# SCH_Arithmetic_Logic_Unit_2021-10-03.net
KiCad netlist of a schematic drawn in EasyEDA
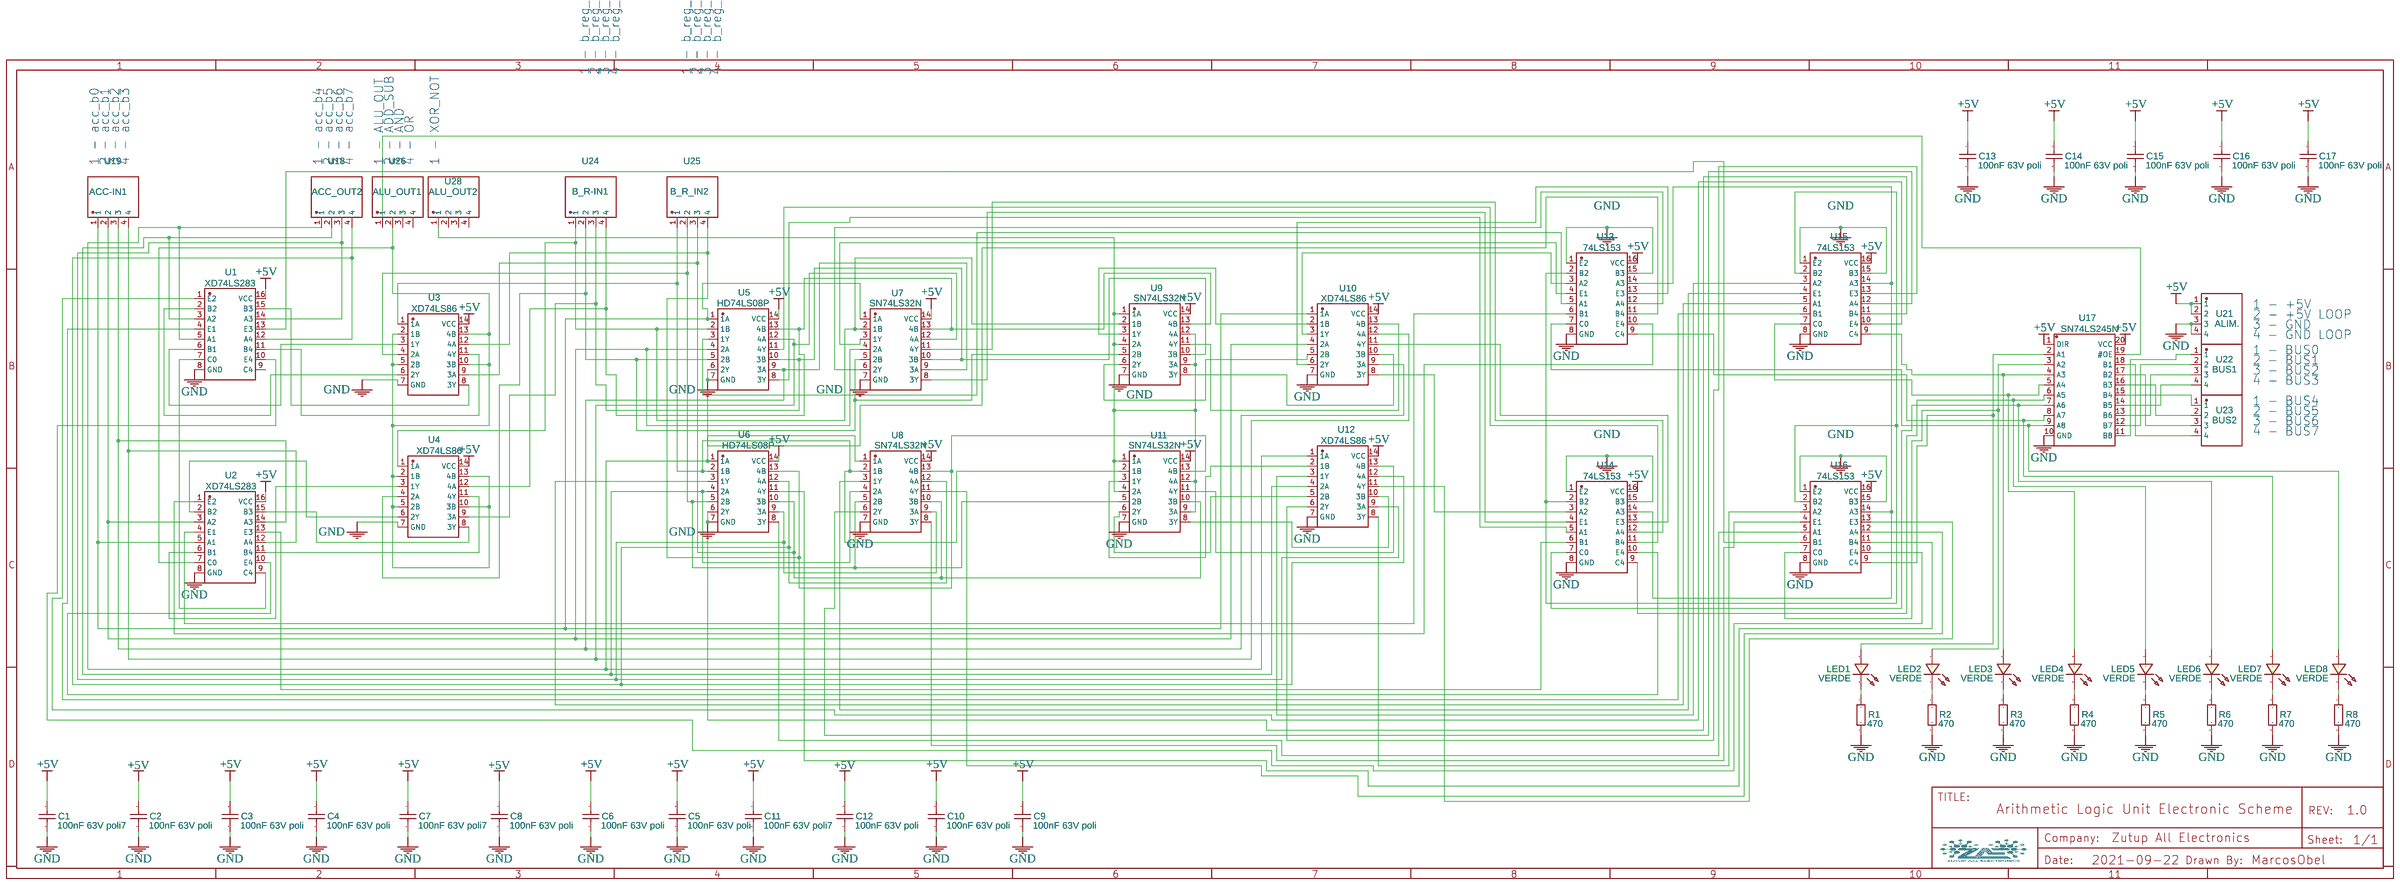
[diagram p0: schematic sheet]

(export (version "E")
  (design (tool "Eeschema 10.0.6"))
  (components
    (comp (ref "C1")
      (value "100nF 63V poli7")
      (fields
        (field (name "BOM_Manufacturer Part") "SR305C105KAR")
        (field (name "BOM_Supplier Part") "C444741")
      )
      (libsource (lib "") (part "SR305C105KAR"))
    )
    (comp (ref "C2")
      (value "100nF 63V poli")
      (fields
        (field (name "BOM_Manufacturer Part") "SR305C105KAR")
        (field (name "BOM_Supplier Part") "C444741")
      )
      (libsource (lib "") (part "SR305C105KAR"))
    )
    (comp (ref "C3")
      (value "100nF 63V poli")
      (fields
        (field (name "BOM_Manufacturer Part") "SR305C105KAR")
        (field (name "BOM_Supplier Part") "C444741")
      )
      (libsource (lib "") (part "SR305C105KAR"))
    )
    (comp (ref "C4")
      (value "100nF 63V poli")
      (fields
        (field (name "BOM_Manufacturer Part") "SR305C105KAR")
        (field (name "BOM_Supplier Part") "C444741")
      )
      (libsource (lib "") (part "SR305C105KAR"))
    )
    (comp (ref "C5")
      (value "100nF 63V poli")
      (fields
        (field (name "BOM_Manufacturer Part") "SR305C105KAR")
        (field (name "BOM_Supplier Part") "C444741")
      )
      (libsource (lib "") (part "SR305C105KAR"))
    )
    (comp (ref "C6")
      (value "100nF 63V poli")
      (fields
        (field (name "BOM_Manufacturer Part") "SR305C105KAR")
        (field (name "BOM_Supplier Part") "C444741")
      )
      (libsource (lib "") (part "SR305C105KAR"))
    )
    (comp (ref "C7")
      (value "100nF 63V poli7")
      (fields
        (field (name "BOM_Manufacturer Part") "SR305C105KAR")
        (field (name "BOM_Supplier Part") "C444741")
      )
      (libsource (lib "") (part "SR305C105KAR"))
    )
    (comp (ref "C8")
      (value "100nF 63V poli")
      (fields
        (field (name "BOM_Manufacturer Part") "SR305C105KAR")
        (field (name "BOM_Supplier Part") "C444741")
      )
      (libsource (lib "") (part "SR305C105KAR"))
    )
    (comp (ref "C9")
      (value "100nF 63V poli")
      (fields
        (field (name "BOM_Manufacturer Part") "SR305C105KAR")
        (field (name "BOM_Supplier Part") "C444741")
      )
      (libsource (lib "") (part "SR305C105KAR"))
    )
    (comp (ref "C10")
      (value "100nF 63V poli")
      (fields
        (field (name "BOM_Manufacturer Part") "SR305C105KAR")
        (field (name "BOM_Supplier Part") "C444741")
      )
      (libsource (lib "") (part "SR305C105KAR"))
    )
    (comp (ref "C11")
      (value "100nF 63V poli7")
      (fields
        (field (name "BOM_Manufacturer Part") "SR305C105KAR")
        (field (name "BOM_Supplier Part") "C444741")
      )
      (libsource (lib "") (part "SR305C105KAR"))
    )
    (comp (ref "C12")
      (value "100nF 63V poli")
      (fields
        (field (name "BOM_Manufacturer Part") "SR305C105KAR")
        (field (name "BOM_Supplier Part") "C444741")
      )
      (libsource (lib "") (part "SR305C105KAR"))
    )
    (comp (ref "C13")
      (value "100nF 63V poli")
      (fields
        (field (name "BOM_Manufacturer Part") "SR305C105KAR")
        (field (name "BOM_Supplier Part") "C444741")
      )
      (libsource (lib "") (part "SR305C105KAR"))
    )
    (comp (ref "C14")
      (value "100nF 63V poli")
      (fields
        (field (name "BOM_Manufacturer Part") "SR305C105KAR")
        (field (name "BOM_Supplier Part") "C444741")
      )
      (libsource (lib "") (part "SR305C105KAR"))
    )
    (comp (ref "C15")
      (value "100nF 63V poli")
      (fields
        (field (name "BOM_Manufacturer Part") "SR305C105KAR")
        (field (name "BOM_Supplier Part") "C444741")
      )
      (libsource (lib "") (part "SR305C105KAR"))
    )
    (comp (ref "C16")
      (value "100nF 63V poli")
      (fields
        (field (name "BOM_Manufacturer Part") "SR305C105KAR")
        (field (name "BOM_Supplier Part") "C444741")
      )
      (libsource (lib "") (part "SR305C105KAR"))
    )
    (comp (ref "C17")
      (value "100nF 63V poli")
      (fields
        (field (name "BOM_Manufacturer Part") "SR305C105KAR")
        (field (name "BOM_Supplier Part") "C444741")
      )
      (libsource (lib "") (part "SR305C105KAR"))
    )
    (comp (ref "LED1")
      (value "VERDE")
      (fields (field (name "BOM_Manufacturer Part") "264-7GD") (field (name "BOM_Supplier Part") "C605465"))
      (libsource (lib "") (part "264-7GD"))
    )
    (comp (ref "LED2")
      (value "VERDE")
      (fields (field (name "BOM_Manufacturer Part") "264-7GD") (field (name "BOM_Supplier Part") "C605465"))
      (libsource (lib "") (part "264-7GD"))
    )
    (comp (ref "LED3")
      (value "VERDE")
      (fields (field (name "BOM_Manufacturer Part") "264-7GD") (field (name "BOM_Supplier Part") "C605465"))
      (libsource (lib "") (part "264-7GD"))
    )
    (comp (ref "LED4")
      (value "VERDE")
      (fields (field (name "BOM_Manufacturer Part") "264-7GD") (field (name "BOM_Supplier Part") "C605465"))
      (libsource (lib "") (part "264-7GD"))
    )
    (comp (ref "LED5")
      (value "VERDE")
      (fields (field (name "BOM_Manufacturer Part") "264-7GD") (field (name "BOM_Supplier Part") "C605465"))
      (libsource (lib "") (part "264-7GD"))
    )
    (comp (ref "LED6")
      (value "VERDE")
      (fields (field (name "BOM_Manufacturer Part") "264-7GD") (field (name "BOM_Supplier Part") "C605465"))
      (libsource (lib "") (part "264-7GD"))
    )
    (comp (ref "LED7")
      (value "VERDE")
      (fields (field (name "BOM_Manufacturer Part") "264-7GD") (field (name "BOM_Supplier Part") "C605465"))
      (libsource (lib "") (part "264-7GD"))
    )
    (comp (ref "LED8")
      (value "VERDE")
      (fields (field (name "BOM_Manufacturer Part") "264-7GD") (field (name "BOM_Supplier Part") "C605465"))
      (libsource (lib "") (part "264-7GD"))
    )
    (comp (ref "R1")
      (value "470")
      (fields
        (field (name "BOM_Manufacturer Part") "CFR02SJ0823A10")
        (field (name "BOM_Supplier Part") "C69876")
      )
      (libsource (lib "") (part "CFR02SJ0823A10"))
    )
    (comp (ref "R2")
      (value "470")
      (fields
        (field (name "BOM_Manufacturer Part") "CFR02SJ0823A10")
        (field (name "BOM_Supplier Part") "C69876")
      )
      (libsource (lib "") (part "CFR02SJ0823A10"))
    )
    (comp (ref "R3")
      (value "470")
      (fields
        (field (name "BOM_Manufacturer Part") "CFR02SJ0823A10")
        (field (name "BOM_Supplier Part") "C69876")
      )
      (libsource (lib "") (part "CFR02SJ0823A10"))
    )
    (comp (ref "R4")
      (value "470")
      (fields
        (field (name "BOM_Manufacturer Part") "CFR02SJ0823A10")
        (field (name "BOM_Supplier Part") "C69876")
      )
      (libsource (lib "") (part "CFR02SJ0823A10"))
    )
    (comp (ref "R5")
      (value "470")
      (fields
        (field (name "BOM_Manufacturer Part") "CFR02SJ0823A10")
        (field (name "BOM_Supplier Part") "C69876")
      )
      (libsource (lib "") (part "CFR02SJ0823A10"))
    )
    (comp (ref "R6")
      (value "470")
      (fields
        (field (name "BOM_Manufacturer Part") "CFR02SJ0823A10")
        (field (name "BOM_Supplier Part") "C69876")
      )
      (libsource (lib "") (part "CFR02SJ0823A10"))
    )
    (comp (ref "R7")
      (value "470")
      (fields
        (field (name "BOM_Manufacturer Part") "CFR02SJ0823A10")
        (field (name "BOM_Supplier Part") "C69876")
      )
      (libsource (lib "") (part "CFR02SJ0823A10"))
    )
    (comp (ref "R8")
      (value "470")
      (fields
        (field (name "BOM_Manufacturer Part") "CFR02SJ0823A10")
        (field (name "BOM_Supplier Part") "C69876")
      )
      (libsource (lib "") (part "CFR02SJ0823A10"))
    )
    (comp (ref "U1")
      (value "XD74LS283")
      (fields (field (name "BOM_Supplier Part") "C561301"))
      (libsource (lib "") (part "XD74LS283"))
    )
    (comp (ref "U2")
      (value "XD74LS283")
      (fields (field (name "BOM_Supplier Part") "C561301"))
      (libsource (lib "") (part "XD74LS283"))
    )
    (comp (ref "U3")
      (value "XD74LS86")
      (fields (field (name "BOM_Supplier Part") "C556290"))
      (libsource (lib "") (part "XD74LS86"))
    )
    (comp (ref "U4")
      (value "XD74LS86")
      (fields (field (name "BOM_Supplier Part") "C556290"))
      (libsource (lib "") (part "XD74LS86"))
    )
    (comp (ref "U5")
      (value "HD74LS08P")
      (fields (field (name "BOM_Supplier Part") "C5270"))
      (libsource (lib "") (part "HD74LS08P"))
    )
    (comp (ref "U6")
      (value "HD74LS08P")
      (fields (field (name "BOM_Supplier Part") "C5270"))
      (libsource (lib "") (part "HD74LS08P"))
    )
    (comp (ref "U7")
      (value "SN74LS32N")
      (fields (field (name "BOM_Supplier Part") "C273644"))
      (libsource (lib "") (part "SN74LS32N"))
    )
    (comp (ref "U8")
      (value "SN74LS32N")
      (fields (field (name "BOM_Supplier Part") "C273644"))
      (libsource (lib "") (part "SN74LS32N"))
    )
    (comp (ref "U9")
      (value "SN74LS32N")
      (fields (field (name "BOM_Supplier Part") "C273644"))
      (libsource (lib "") (part "SN74LS32N"))
    )
    (comp (ref "U10")
      (value "XD74LS86")
      (fields (field (name "BOM_Supplier Part") "C556290"))
      (libsource (lib "") (part "XD74LS86"))
    )
    (comp (ref "U11")
      (value "SN74LS32N")
      (fields (field (name "BOM_Supplier Part") "C273644"))
      (libsource (lib "") (part "SN74LS32N"))
    )
    (comp (ref "U12")
      (value "XD74LS86")
      (fields (field (name "BOM_Supplier Part") "C556290"))
      (libsource (lib "") (part "XD74LS86"))
    )
    (comp (ref "U13")
      (value "74LS153")
      (fields (field (name "BOM_Manufacturer Part") "XD74LS283") (field (name "BOM_Supplier Part") "C561301"))
      (libsource (lib "") (part "XD74LS283"))
    )
    (comp (ref "U14")
      (value "74LS153")
      (fields (field (name "BOM_Manufacturer Part") "XD74LS283") (field (name "BOM_Supplier Part") "C561301"))
      (libsource (lib "") (part "XD74LS283"))
    )
    (comp (ref "U15")
      (value "74LS153")
      (fields (field (name "BOM_Manufacturer Part") "XD74LS283") (field (name "BOM_Supplier Part") "C561301"))
      (libsource (lib "") (part "XD74LS283"))
    )
    (comp (ref "U16")
      (value "74LS153")
      (fields (field (name "BOM_Manufacturer Part") "XD74LS283") (field (name "BOM_Supplier Part") "C561301"))
      (libsource (lib "") (part "XD74LS283"))
    )
    (comp (ref "U17")
      (value "SN74LS245N")
      (fields (field (name "BOM_Supplier Part") "C352966"))
      (libsource (lib "") (part "SN74LS245N"))
    )
    (comp (ref "U18")
      (value "ACC_OUT2")
      (fields (field (name "BOM_Manufacturer Part") "171825-4") (field (name "BOM_Supplier Part") "C210162"))
      (libsource (lib "") (part "171825-4"))
    )
    (comp (ref "U19")
      (value "ACC-IN1")
      (fields (field (name "BOM_Manufacturer Part") "171825-4") (field (name "BOM_Supplier Part") "C210162"))
      (libsource (lib "") (part "171825-4"))
    )
    (comp (ref "U21")
      (value "ALIM.")
      (fields (field (name "BOM_Manufacturer Part") "171825-4") (field (name "BOM_Supplier Part") "C210162"))
      (libsource (lib "") (part "171825-4_1"))
    )
    (comp (ref "U22")
      (value "BUS1")
      (fields (field (name "BOM_Manufacturer Part") "171825-4") (field (name "BOM_Supplier Part") "C210162"))
      (libsource (lib "") (part "171825-4_1"))
    )
    (comp (ref "U23")
      (value "BUS2")
      (fields (field (name "BOM_Manufacturer Part") "171825-4") (field (name "BOM_Supplier Part") "C210162"))
      (libsource (lib "") (part "171825-4_1"))
    )
    (comp (ref "U24")
      (value "B_R-IN1")
      (fields (field (name "BOM_Manufacturer Part") "171825-4") (field (name "BOM_Supplier Part") "C210162"))
      (libsource (lib "") (part "171825-4"))
    )
    (comp (ref "U25")
      (value "B_R_IN2")
      (fields (field (name "BOM_Manufacturer Part") "171825-4") (field (name "BOM_Supplier Part") "C210162"))
      (libsource (lib "") (part "171825-4"))
    )
    (comp (ref "U26")
      (value "ALU_OUT1")
      (fields (field (name "BOM_Manufacturer Part") "171825-4") (field (name "BOM_Supplier Part") "C210162"))
      (libsource (lib "") (part "171825-4"))
    )
    (comp (ref "U28")
      (value "ALU_OUT2")
      (fields (field (name "BOM_Manufacturer Part") "171825-4") (field (name "BOM_Supplier Part") "C210162"))
      (libsource (lib "") (part "171825-4"))
    )
  )
  (nets
    (net (code "1") (name "+5V") (class "Default")
      (node (ref "C1") (pin "1") (pinfunction "1_1") (pintype "input"))
      (node (ref "C10") (pin "1") (pinfunction "1_1") (pintype "input"))
      (node (ref "C11") (pin "1") (pinfunction "1_1") (pintype "input"))
      (node (ref "C12") (pin "1") (pinfunction "1_1") (pintype "input"))
      (node (ref "C13") (pin "1") (pinfunction "1_1") (pintype "input"))
      (node (ref "C14") (pin "1") (pinfunction "1_1") (pintype "input"))
      (node (ref "C15") (pin "1") (pinfunction "1_1") (pintype "input"))
      (node (ref "C16") (pin "1") (pinfunction "1_1") (pintype "input"))
      (node (ref "C17") (pin "1") (pinfunction "1_1") (pintype "input"))
      (node (ref "C2") (pin "1") (pinfunction "1_1") (pintype "input"))
      (node (ref "C3") (pin "1") (pinfunction "1_1") (pintype "input"))
      (node (ref "C4") (pin "1") (pinfunction "1_1") (pintype "input"))
      (node (ref "C5") (pin "1") (pinfunction "1_1") (pintype "input"))
      (node (ref "C6") (pin "1") (pinfunction "1_1") (pintype "input"))
      (node (ref "C7") (pin "1") (pinfunction "1_1") (pintype "input"))
      (node (ref "C8") (pin "1") (pinfunction "1_1") (pintype "input"))
      (node (ref "C9") (pin "1") (pinfunction "1_1") (pintype "input"))
      (node (ref "U1") (pin "16") (pinfunction "VCC_16") (pintype "unspecified"))
      (node (ref "U10") (pin "14") (pinfunction "VCC_14") (pintype "unspecified"))
      (node (ref "U11") (pin "14") (pinfunction "VCC_14") (pintype "unspecified"))
      (node (ref "U12") (pin "14") (pinfunction "VCC_14") (pintype "unspecified"))
      (node (ref "U13") (pin "16") (pinfunction "VCC_16") (pintype "unspecified"))
      (node (ref "U14") (pin "16") (pinfunction "VCC_16") (pintype "unspecified"))
      (node (ref "U15") (pin "16") (pinfunction "VCC_16") (pintype "unspecified"))
      (node (ref "U16") (pin "16") (pinfunction "VCC_16") (pintype "unspecified"))
      (node (ref "U17") (pin "1") (pinfunction "DIR_1") (pintype "unspecified"))
      (node (ref "U17") (pin "20") (pinfunction "VCC_20") (pintype "unspecified"))
      (node (ref "U2") (pin "16") (pinfunction "VCC_16") (pintype "unspecified"))
      (node (ref "U21") (pin "1") (pinfunction "1_1") (pintype "unspecified"))
      (node (ref "U21") (pin "2") (pinfunction "2_2") (pintype "unspecified"))
      (node (ref "U3") (pin "14") (pinfunction "VCC_14") (pintype "unspecified"))
      (node (ref "U4") (pin "14") (pinfunction "VCC_14") (pintype "unspecified"))
      (node (ref "U5") (pin "14") (pinfunction "VCC_14") (pintype "unspecified"))
      (node (ref "U6") (pin "14") (pinfunction "VCC_14") (pintype "unspecified"))
      (node (ref "U7") (pin "14") (pinfunction "VCC_14") (pintype "unspecified"))
      (node (ref "U8") (pin "14") (pinfunction "VCC_14") (pintype "unspecified"))
      (node (ref "U9") (pin "14") (pinfunction "VCC_14") (pintype "unspecified"))
    )
    (net (code "2") (name "GND") (class "Default")
      (node (ref "C1") (pin "2") (pinfunction "2_2") (pintype "input"))
      (node (ref "C10") (pin "2") (pinfunction "2_2") (pintype "input"))
      (node (ref "C11") (pin "2") (pinfunction "2_2") (pintype "input"))
      (node (ref "C12") (pin "2") (pinfunction "2_2") (pintype "input"))
      (node (ref "C13") (pin "2") (pinfunction "2_2") (pintype "input"))
      (node (ref "C14") (pin "2") (pinfunction "2_2") (pintype "input"))
      (node (ref "C15") (pin "2") (pinfunction "2_2") (pintype "input"))
      (node (ref "C16") (pin "2") (pinfunction "2_2") (pintype "input"))
      (node (ref "C17") (pin "2") (pinfunction "2_2") (pintype "input"))
      (node (ref "C2") (pin "2") (pinfunction "2_2") (pintype "input"))
      (node (ref "C3") (pin "2") (pinfunction "2_2") (pintype "input"))
      (node (ref "C4") (pin "2") (pinfunction "2_2") (pintype "input"))
      (node (ref "C5") (pin "2") (pinfunction "2_2") (pintype "input"))
      (node (ref "C6") (pin "2") (pinfunction "2_2") (pintype "input"))
      (node (ref "C7") (pin "2") (pinfunction "2_2") (pintype "input"))
      (node (ref "C8") (pin "2") (pinfunction "2_2") (pintype "input"))
      (node (ref "C9") (pin "2") (pinfunction "2_2") (pintype "input"))
      (node (ref "R1") (pin "2") (pinfunction "2_2") (pintype "input"))
      (node (ref "R2") (pin "2") (pinfunction "2_2") (pintype "input"))
      (node (ref "R3") (pin "2") (pinfunction "2_2") (pintype "input"))
      (node (ref "R4") (pin "2") (pinfunction "2_2") (pintype "input"))
      (node (ref "R5") (pin "2") (pinfunction "2_2") (pintype "input"))
      (node (ref "R6") (pin "2") (pinfunction "2_2") (pintype "input"))
      (node (ref "R7") (pin "2") (pinfunction "2_2") (pintype "input"))
      (node (ref "R8") (pin "2") (pinfunction "2_2") (pintype "input"))
      (node (ref "U1") (pin "8") (pinfunction "GND_8") (pintype "unspecified"))
      (node (ref "U10") (pin "7") (pinfunction "GND_7") (pintype "unspecified"))
      (node (ref "U11") (pin "7") (pinfunction "GND_7") (pintype "unspecified"))
      (node (ref "U12") (pin "7") (pinfunction "GND_7") (pintype "unspecified"))
      (node (ref "U13") (pin "1") (pinfunction "E2_1") (pintype "unspecified"))
      (node (ref "U13") (pin "11") (pinfunction "B4_11") (pintype "unspecified"))
      (node (ref "U13") (pin "15") (pinfunction "B3_15") (pintype "unspecified"))
      (node (ref "U13") (pin "8") (pinfunction "GND_8") (pintype "unspecified"))
      (node (ref "U14") (pin "1") (pinfunction "E2_1") (pintype "unspecified"))
      (node (ref "U14") (pin "15") (pinfunction "B3_15") (pintype "unspecified"))
      (node (ref "U14") (pin "8") (pinfunction "GND_8") (pintype "unspecified"))
      (node (ref "U15") (pin "1") (pinfunction "E2_1") (pintype "unspecified"))
      (node (ref "U15") (pin "11") (pinfunction "B4_11") (pintype "unspecified"))
      (node (ref "U15") (pin "15") (pinfunction "B3_15") (pintype "unspecified"))
      (node (ref "U15") (pin "8") (pinfunction "GND_8") (pintype "unspecified"))
      (node (ref "U16") (pin "1") (pinfunction "E2_1") (pintype "unspecified"))
      (node (ref "U16") (pin "15") (pinfunction "B3_15") (pintype "unspecified"))
      (node (ref "U16") (pin "8") (pinfunction "GND_8") (pintype "unspecified"))
      (node (ref "U17") (pin "10") (pinfunction "GND_10") (pintype "unspecified"))
      (node (ref "U2") (pin "8") (pinfunction "GND_8") (pintype "unspecified"))
      (node (ref "U21") (pin "3") (pinfunction "3_3") (pintype "unspecified"))
      (node (ref "U21") (pin "4") (pinfunction "4_4") (pintype "unspecified"))
      (node (ref "U3") (pin "7") (pinfunction "GND_7") (pintype "unspecified"))
      (node (ref "U4") (pin "7") (pinfunction "GND_7") (pintype "unspecified"))
      (node (ref "U5") (pin "6") (pinfunction "2Y_6") (pintype "unspecified"))
      (node (ref "U5") (pin "7") (pinfunction "GND_7") (pintype "unspecified"))
      (node (ref "U6") (pin "6") (pinfunction "2Y_6") (pintype "unspecified"))
      (node (ref "U6") (pin "7") (pinfunction "GND_7") (pintype "unspecified"))
      (node (ref "U7") (pin "7") (pinfunction "GND_7") (pintype "unspecified"))
      (node (ref "U8") (pin "7") (pinfunction "GND_7") (pintype "unspecified"))
      (node (ref "U9") (pin "7") (pinfunction "GND_7") (pintype "unspecified"))
    )
    (net (code "3") (name "Net-(LED1-+)") (class "Default")
      (node (ref "LED1") (pin "2") (pinfunction "+_2") (pintype "unspecified"))
      (node (ref "U16") (pin "9") (pinfunction "C4_9") (pintype "unspecified"))
      (node (ref "U17") (pin "2") (pinfunction "A1_2") (pintype "unspecified"))
    )
    (net (code "4") (name "Net-(LED1--)") (class "Default")
      (node (ref "LED1") (pin "1") (pinfunction "-_1") (pintype "unspecified"))
      (node (ref "R1") (pin "1") (pinfunction "1_1") (pintype "input"))
    )
    (net (code "5") (name "Net-(LED2-+)") (class "Default")
      (node (ref "LED2") (pin "2") (pinfunction "+_2") (pintype "unspecified"))
      (node (ref "U16") (pin "7") (pinfunction "C0_7") (pintype "unspecified"))
      (node (ref "U17") (pin "3") (pinfunction "A2_3") (pintype "unspecified"))
    )
    (net (code "6") (name "Net-(LED2--)") (class "Default")
      (node (ref "LED2") (pin "1") (pinfunction "-_1") (pintype "unspecified"))
      (node (ref "R2") (pin "1") (pinfunction "1_1") (pintype "input"))
    )
    (net (code "7") (name "Net-(LED3-+)") (class "Default")
      (node (ref "LED3") (pin "2") (pinfunction "+_2") (pintype "unspecified"))
      (node (ref "U15") (pin "9") (pinfunction "C4_9") (pintype "unspecified"))
      (node (ref "U17") (pin "4") (pinfunction "A3_4") (pintype "unspecified"))
    )
    (net (code "8") (name "Net-(LED3--)") (class "Default")
      (node (ref "LED3") (pin "1") (pinfunction "-_1") (pintype "unspecified"))
      (node (ref "R3") (pin "1") (pinfunction "1_1") (pintype "input"))
    )
    (net (code "9") (name "Net-(LED4-+)") (class "Default")
      (node (ref "LED4") (pin "2") (pinfunction "+_2") (pintype "unspecified"))
      (node (ref "U15") (pin "7") (pinfunction "C0_7") (pintype "unspecified"))
      (node (ref "U17") (pin "5") (pinfunction "A4_5") (pintype "unspecified"))
    )
    (net (code "10") (name "Net-(LED4--)") (class "Default")
      (node (ref "LED4") (pin "1") (pinfunction "-_1") (pintype "unspecified"))
      (node (ref "R4") (pin "1") (pinfunction "1_1") (pintype "input"))
    )
    (net (code "11") (name "Net-(LED5-+)") (class "Default")
      (node (ref "LED5") (pin "2") (pinfunction "+_2") (pintype "unspecified"))
      (node (ref "U14") (pin "9") (pinfunction "C4_9") (pintype "unspecified"))
      (node (ref "U17") (pin "6") (pinfunction "A5_6") (pintype "unspecified"))
    )
    (net (code "12") (name "Net-(LED5--)") (class "Default")
      (node (ref "LED5") (pin "1") (pinfunction "-_1") (pintype "unspecified"))
      (node (ref "R5") (pin "1") (pinfunction "1_1") (pintype "input"))
    )
    (net (code "13") (name "Net-(LED6-+)") (class "Default")
      (node (ref "LED6") (pin "2") (pinfunction "+_2") (pintype "unspecified"))
      (node (ref "U14") (pin "7") (pinfunction "C0_7") (pintype "unspecified"))
      (node (ref "U17") (pin "7") (pinfunction "A6_7") (pintype "unspecified"))
    )
    (net (code "14") (name "Net-(LED6--)") (class "Default")
      (node (ref "LED6") (pin "1") (pinfunction "-_1") (pintype "unspecified"))
      (node (ref "R6") (pin "1") (pinfunction "1_1") (pintype "input"))
    )
    (net (code "15") (name "Net-(LED7-+)") (class "Default")
      (node (ref "LED7") (pin "2") (pinfunction "+_2") (pintype "unspecified"))
      (node (ref "U13") (pin "9") (pinfunction "C4_9") (pintype "unspecified"))
      (node (ref "U17") (pin "8") (pinfunction "A7_8") (pintype "unspecified"))
    )
    (net (code "16") (name "Net-(LED7--)") (class "Default")
      (node (ref "LED7") (pin "1") (pinfunction "-_1") (pintype "unspecified"))
      (node (ref "R7") (pin "1") (pinfunction "1_1") (pintype "input"))
    )
    (net (code "17") (name "Net-(LED8-+)") (class "Default")
      (node (ref "LED8") (pin "2") (pinfunction "+_2") (pintype "unspecified"))
      (node (ref "U13") (pin "7") (pinfunction "C0_7") (pintype "unspecified"))
      (node (ref "U17") (pin "9") (pinfunction "A8_9") (pintype "unspecified"))
    )
    (net (code "18") (name "Net-(LED8--)") (class "Default")
      (node (ref "LED8") (pin "1") (pinfunction "-_1") (pintype "unspecified"))
      (node (ref "R8") (pin "1") (pinfunction "1_1") (pintype "input"))
    )
    (net (code "19") (name "Net-(U1-A1)") (class "Default")
      (node (ref "U1") (pin "5") (pinfunction "A1_5") (pintype "unspecified"))
      (node (ref "U12") (pin "1") (pinfunction "1A_1") (pintype "unspecified"))
      (node (ref "U18") (pin "1") (pinfunction "1_1") (pintype "unspecified"))
      (node (ref "U6") (pin "1") (pinfunction "1A_1") (pintype "unspecified"))
      (node (ref "U8") (pin "1") (pinfunction "1A_1") (pintype "unspecified"))
    )
    (net (code "20") (name "Net-(U1-A2)") (class "Default")
      (node (ref "U1") (pin "3") (pinfunction "A2_3") (pintype "unspecified"))
      (node (ref "U12") (pin "4") (pinfunction "2A_4") (pintype "unspecified"))
      (node (ref "U18") (pin "2") (pinfunction "2_2") (pintype "unspecified"))
      (node (ref "U6") (pin "4") (pinfunction "2A_4") (pintype "unspecified"))
      (node (ref "U8") (pin "4") (pinfunction "2A_4") (pintype "unspecified"))
    )
    (net (code "21") (name "Net-(U1-A3)") (class "Default")
      (node (ref "U1") (pin "14") (pinfunction "A3_14") (pintype "unspecified"))
      (node (ref "U12") (pin "9") (pinfunction "3A_9") (pintype "unspecified"))
      (node (ref "U18") (pin "3") (pinfunction "3_3") (pintype "unspecified"))
      (node (ref "U6") (pin "9") (pinfunction "3A_9") (pintype "unspecified"))
      (node (ref "U8") (pin "9") (pinfunction "3A_9") (pintype "unspecified"))
    )
    (net (code "22") (name "Net-(U1-A4)") (class "Default")
      (node (ref "U1") (pin "12") (pinfunction "A4_12") (pintype "unspecified"))
      (node (ref "U12") (pin "12") (pinfunction "4A_12") (pintype "unspecified"))
      (node (ref "U18") (pin "4") (pinfunction "4_4") (pintype "unspecified"))
      (node (ref "U6") (pin "12") (pinfunction "4A_12") (pintype "unspecified"))
      (node (ref "U8") (pin "12") (pinfunction "4A_12") (pintype "unspecified"))
    )
    (net (code "23") (name "Net-(U1-B1)") (class "Default")
      (node (ref "U1") (pin "6") (pinfunction "B1_6") (pintype "unspecified"))
      (node (ref "U3") (pin "3") (pinfunction "1Y_3") (pintype "unspecified"))
    )
    (net (code "24") (name "Net-(U1-B2)") (class "Default")
      (node (ref "U1") (pin "2") (pinfunction "B2_2") (pintype "unspecified"))
      (node (ref "U3") (pin "6") (pinfunction "2Y_6") (pintype "unspecified"))
    )
    (net (code "25") (name "Net-(U1-B3)") (class "Default")
      (node (ref "U1") (pin "15") (pinfunction "B3_15") (pintype "unspecified"))
      (node (ref "U3") (pin "8") (pinfunction "3Y_8") (pintype "unspecified"))
    )
    (net (code "26") (name "Net-(U1-B4)") (class "Default")
      (node (ref "U1") (pin "11") (pinfunction "B4_11") (pintype "unspecified"))
      (node (ref "U3") (pin "11") (pinfunction "4Y_11") (pintype "unspecified"))
    )
    (net (code "27") (name "Net-(U1-C0)") (class "Default")
      (node (ref "U1") (pin "7") (pinfunction "C0_7") (pintype "unspecified"))
      (node (ref "U2") (pin "9") (pinfunction "C4_9") (pintype "unspecified"))
    )
    (net (code "28") (name "Net-(U1-E1)") (class "Default")
      (node (ref "U1") (pin "4") (pinfunction "E1_4") (pintype "unspecified"))
      (node (ref "U15") (pin "6") (pinfunction "B1_6") (pintype "unspecified"))
    )
    (net (code "29") (name "Net-(U1-E2)") (class "Default")
      (node (ref "U1") (pin "1") (pinfunction "E2_1") (pintype "unspecified"))
      (node (ref "U15") (pin "10") (pinfunction "E4_10") (pintype "unspecified"))
    )
    (net (code "30") (name "Net-(U1-E3)") (class "Default")
      (node (ref "U1") (pin "13") (pinfunction "E3_13") (pintype "unspecified"))
      (node (ref "U16") (pin "6") (pinfunction "B1_6") (pintype "unspecified"))
    )
    (net (code "31") (name "Net-(U1-E4)") (class "Default")
      (node (ref "U1") (pin "10") (pinfunction "E4_10") (pintype "unspecified"))
      (node (ref "U16") (pin "10") (pinfunction "E4_10") (pintype "unspecified"))
    )
    (net (code "32") (name "Net-(U2-B1)") (class "Default")
      (node (ref "U2") (pin "6") (pinfunction "B1_6") (pintype "unspecified"))
      (node (ref "U4") (pin "3") (pinfunction "1Y_3") (pintype "unspecified"))
    )
    (net (code "33") (name "Net-(U2-B2)") (class "Default")
      (node (ref "U2") (pin "2") (pinfunction "B2_2") (pintype "unspecified"))
      (node (ref "U4") (pin "6") (pinfunction "2Y_6") (pintype "unspecified"))
    )
    (net (code "34") (name "Net-(U2-B3)") (class "Default")
      (node (ref "U2") (pin "15") (pinfunction "B3_15") (pintype "unspecified"))
      (node (ref "U4") (pin "8") (pinfunction "3Y_8") (pintype "unspecified"))
    )
    (net (code "35") (name "Net-(U2-B4)") (class "Default")
      (node (ref "U2") (pin "11") (pinfunction "B4_11") (pintype "unspecified"))
      (node (ref "U4") (pin "11") (pinfunction "4Y_11") (pintype "unspecified"))
    )
    (net (code "36") (name "Net-(U2-C0)") (class "Default")
      (node (ref "U2") (pin "7") (pinfunction "C0_7") (pintype "unspecified"))
      (node (ref "U26") (pin "2") (pinfunction "2_2") (pintype "unspecified"))
      (node (ref "U3") (pin "10") (pinfunction "3B_10") (pintype "unspecified"))
      (node (ref "U3") (pin "13") (pinfunction "4B_13") (pintype "unspecified"))
      (node (ref "U3") (pin "2") (pinfunction "1B_2") (pintype "unspecified"))
      (node (ref "U3") (pin "5") (pinfunction "2B_5") (pintype "unspecified"))
      (node (ref "U4") (pin "10") (pinfunction "3B_10") (pintype "unspecified"))
      (node (ref "U4") (pin "13") (pinfunction "4B_13") (pintype "unspecified"))
      (node (ref "U4") (pin "2") (pinfunction "1B_2") (pintype "unspecified"))
      (node (ref "U4") (pin "5") (pinfunction "2B_5") (pintype "unspecified"))
    )
    (net (code "37") (name "Net-(U4-1A)") (class "Default")
      (node (ref "U24") (pin "1") (pinfunction "1_1") (pintype "unspecified"))
      (node (ref "U4") (pin "1") (pinfunction "1A_1") (pintype "unspecified"))
      (node (ref "U5") (pin "2") (pinfunction "1B_2") (pintype "unspecified"))
      (node (ref "U7") (pin "2") (pinfunction "1B_2") (pintype "unspecified"))
      (node (ref "U9") (pin "2") (pinfunction "1B_2") (pintype "unspecified"))
    )
    (net (code "38") (name "Net-(U4-2A)") (class "Default")
      (node (ref "U24") (pin "2") (pinfunction "2_2") (pintype "unspecified"))
      (node (ref "U4") (pin "4") (pinfunction "2A_4") (pintype "unspecified"))
      (node (ref "U5") (pin "5") (pinfunction "2B_5") (pintype "unspecified"))
      (node (ref "U7") (pin "5") (pinfunction "2B_5") (pintype "unspecified"))
      (node (ref "U9") (pin "5") (pinfunction "2B_5") (pintype "unspecified"))
    )
    (net (code "39") (name "Net-(U4-3A)") (class "Default")
      (node (ref "U24") (pin "3") (pinfunction "3_3") (pintype "unspecified"))
      (node (ref "U4") (pin "9") (pinfunction "3A_9") (pintype "unspecified"))
      (node (ref "U5") (pin "10") (pinfunction "3B_10") (pintype "unspecified"))
      (node (ref "U7") (pin "10") (pinfunction "3B_10") (pintype "unspecified"))
      (node (ref "U9") (pin "10") (pinfunction "3B_10") (pintype "unspecified"))
    )
    (net (code "40") (name "Net-(U4-4A)") (class "Default")
      (node (ref "U24") (pin "4") (pinfunction "4_4") (pintype "unspecified"))
      (node (ref "U4") (pin "12") (pinfunction "4A_12") (pintype "unspecified"))
      (node (ref "U5") (pin "13") (pinfunction "4B_13") (pintype "unspecified"))
      (node (ref "U7") (pin "13") (pinfunction "4B_13") (pintype "unspecified"))
      (node (ref "U9") (pin "13") (pinfunction "4B_13") (pintype "unspecified"))
    )
    (net (code "41") (name "Net-(U10-1A)") (class "Default")
      (node (ref "U10") (pin "1") (pinfunction "1A_1") (pintype "unspecified"))
      (node (ref "U19") (pin "1") (pinfunction "1_1") (pintype "unspecified"))
      (node (ref "U2") (pin "5") (pinfunction "A1_5") (pintype "unspecified"))
      (node (ref "U5") (pin "1") (pinfunction "1A_1") (pintype "unspecified"))
      (node (ref "U7") (pin "1") (pinfunction "1A_1") (pintype "unspecified"))
    )
    (net (code "42") (name "Net-(U10-1B)") (class "Default")
      (node (ref "U10") (pin "2") (pinfunction "1B_2") (pintype "unspecified"))
      (node (ref "U9") (pin "3") (pinfunction "1Y_3") (pintype "unspecified"))
    )
    (net (code "43") (name "Net-(U10-1Y)") (class "Default")
      (node (ref "U10") (pin "3") (pinfunction "1Y_3") (pintype "unspecified"))
      (node (ref "U13") (pin "3") (pinfunction "A2_3") (pintype "unspecified"))
    )
    (net (code "44") (name "Net-(U10-2A)") (class "Default")
      (node (ref "U10") (pin "4") (pinfunction "2A_4") (pintype "unspecified"))
      (node (ref "U19") (pin "2") (pinfunction "2_2") (pintype "unspecified"))
      (node (ref "U2") (pin "3") (pinfunction "A2_3") (pintype "unspecified"))
      (node (ref "U5") (pin "4") (pinfunction "2A_4") (pintype "unspecified"))
      (node (ref "U7") (pin "4") (pinfunction "2A_4") (pintype "unspecified"))
    )
    (net (code "45") (name "Net-(U10-2B)") (class "Default")
      (node (ref "U10") (pin "5") (pinfunction "2B_5") (pintype "unspecified"))
      (node (ref "U9") (pin "6") (pinfunction "2Y_6") (pintype "unspecified"))
    )
    (net (code "46") (name "Net-(U10-2Y)") (class "Default")
      (node (ref "U10") (pin "6") (pinfunction "2Y_6") (pintype "unspecified"))
      (node (ref "U13") (pin "13") (pinfunction "E3_13") (pintype "unspecified"))
    )
    (net (code "47") (name "Net-(U10-3A)") (class "Default")
      (node (ref "U10") (pin "9") (pinfunction "3A_9") (pintype "unspecified"))
      (node (ref "U19") (pin "3") (pinfunction "3_3") (pintype "unspecified"))
      (node (ref "U2") (pin "14") (pinfunction "A3_14") (pintype "unspecified"))
      (node (ref "U5") (pin "9") (pinfunction "3A_9") (pintype "unspecified"))
      (node (ref "U7") (pin "9") (pinfunction "3A_9") (pintype "unspecified"))
    )
    (net (code "48") (name "Net-(U10-3B)") (class "Default")
      (node (ref "U10") (pin "10") (pinfunction "3B_10") (pintype "unspecified"))
      (node (ref "U9") (pin "8") (pinfunction "3Y_8") (pintype "unspecified"))
    )
    (net (code "49") (name "Net-(U10-3Y)") (class "Default")
      (node (ref "U10") (pin "8") (pinfunction "3Y_8") (pintype "unspecified"))
      (node (ref "U14") (pin "3") (pinfunction "A2_3") (pintype "unspecified"))
    )
    (net (code "50") (name "Net-(U10-4A)") (class "Default")
      (node (ref "U10") (pin "12") (pinfunction "4A_12") (pintype "unspecified"))
      (node (ref "U19") (pin "4") (pinfunction "4_4") (pintype "unspecified"))
      (node (ref "U2") (pin "12") (pinfunction "A4_12") (pintype "unspecified"))
      (node (ref "U5") (pin "12") (pinfunction "4A_12") (pintype "unspecified"))
      (node (ref "U7") (pin "12") (pinfunction "4A_12") (pintype "unspecified"))
    )
    (net (code "51") (name "Net-(U10-4B)") (class "Default")
      (node (ref "U10") (pin "13") (pinfunction "4B_13") (pintype "unspecified"))
      (node (ref "U9") (pin "11") (pinfunction "4Y_11") (pintype "unspecified"))
    )
    (net (code "52") (name "Net-(U10-4Y)") (class "Default")
      (node (ref "U10") (pin "11") (pinfunction "4Y_11") (pintype "unspecified"))
      (node (ref "U14") (pin "13") (pinfunction "E3_13") (pintype "unspecified"))
    )
    (net (code "53") (name "Net-(U11-1A)") (class "Default")
      (node (ref "U11") (pin "1") (pinfunction "1A_1") (pintype "unspecified"))
      (node (ref "U11") (pin "12") (pinfunction "4A_12") (pintype "unspecified"))
      (node (ref "U11") (pin "4") (pinfunction "2A_4") (pintype "unspecified"))
      (node (ref "U11") (pin "9") (pinfunction "3A_9") (pintype "unspecified"))
      (node (ref "U28") (pin "1") (pinfunction "1_1") (pintype "unspecified"))
      (node (ref "U9") (pin "1") (pinfunction "1A_1") (pintype "unspecified"))
      (node (ref "U9") (pin "12") (pinfunction "4A_12") (pintype "unspecified"))
      (node (ref "U9") (pin "4") (pinfunction "2A_4") (pintype "unspecified"))
      (node (ref "U9") (pin "9") (pinfunction "3A_9") (pintype "unspecified"))
    )
    (net (code "54") (name "Net-(U11-1B)") (class "Default")
      (node (ref "U11") (pin "2") (pinfunction "1B_2") (pintype "unspecified"))
      (node (ref "U25") (pin "1") (pinfunction "1_1") (pintype "unspecified"))
      (node (ref "U3") (pin "1") (pinfunction "1A_1") (pintype "unspecified"))
      (node (ref "U6") (pin "2") (pinfunction "1B_2") (pintype "unspecified"))
      (node (ref "U8") (pin "2") (pinfunction "1B_2") (pintype "unspecified"))
    )
    (net (code "55") (name "Net-(U11-1Y)") (class "Default")
      (node (ref "U11") (pin "3") (pinfunction "1Y_3") (pintype "unspecified"))
      (node (ref "U12") (pin "2") (pinfunction "1B_2") (pintype "unspecified"))
    )
    (net (code "56") (name "Net-(U11-2B)") (class "Default")
      (node (ref "U11") (pin "5") (pinfunction "2B_5") (pintype "unspecified"))
      (node (ref "U25") (pin "2") (pinfunction "2_2") (pintype "unspecified"))
      (node (ref "U3") (pin "4") (pinfunction "2A_4") (pintype "unspecified"))
      (node (ref "U6") (pin "5") (pinfunction "2B_5") (pintype "unspecified"))
      (node (ref "U8") (pin "5") (pinfunction "2B_5") (pintype "unspecified"))
    )
    (net (code "57") (name "Net-(U11-2Y)") (class "Default")
      (node (ref "U11") (pin "6") (pinfunction "2Y_6") (pintype "unspecified"))
      (node (ref "U12") (pin "5") (pinfunction "2B_5") (pintype "unspecified"))
    )
    (net (code "58") (name "Net-(U11-3B)") (class "Default")
      (node (ref "U11") (pin "10") (pinfunction "3B_10") (pintype "unspecified"))
      (node (ref "U25") (pin "3") (pinfunction "3_3") (pintype "unspecified"))
      (node (ref "U3") (pin "9") (pinfunction "3A_9") (pintype "unspecified"))
      (node (ref "U6") (pin "10") (pinfunction "3B_10") (pintype "unspecified"))
      (node (ref "U8") (pin "10") (pinfunction "3B_10") (pintype "unspecified"))
    )
    (net (code "59") (name "Net-(U11-3Y)") (class "Default")
      (node (ref "U11") (pin "8") (pinfunction "3Y_8") (pintype "unspecified"))
      (node (ref "U12") (pin "10") (pinfunction "3B_10") (pintype "unspecified"))
    )
    (net (code "60") (name "Net-(U11-4B)") (class "Default")
      (node (ref "U11") (pin "13") (pinfunction "4B_13") (pintype "unspecified"))
      (node (ref "U25") (pin "4") (pinfunction "4_4") (pintype "unspecified"))
      (node (ref "U3") (pin "12") (pinfunction "4A_12") (pintype "unspecified"))
      (node (ref "U6") (pin "13") (pinfunction "4B_13") (pintype "unspecified"))
      (node (ref "U8") (pin "13") (pinfunction "4B_13") (pintype "unspecified"))
    )
    (net (code "61") (name "Net-(U11-4Y)") (class "Default")
      (node (ref "U11") (pin "11") (pinfunction "4Y_11") (pintype "unspecified"))
      (node (ref "U12") (pin "13") (pinfunction "4B_13") (pintype "unspecified"))
    )
    (net (code "62") (name "Net-(U12-1Y)") (class "Default")
      (node (ref "U12") (pin "3") (pinfunction "1Y_3") (pintype "unspecified"))
      (node (ref "U15") (pin "3") (pinfunction "A2_3") (pintype "unspecified"))
    )
    (net (code "63") (name "Net-(U12-2Y)") (class "Default")
      (node (ref "U12") (pin "6") (pinfunction "2Y_6") (pintype "unspecified"))
      (node (ref "U15") (pin "13") (pinfunction "E3_13") (pintype "unspecified"))
    )
    (net (code "64") (name "Net-(U12-3Y)") (class "Default")
      (node (ref "U12") (pin "8") (pinfunction "3Y_8") (pintype "unspecified"))
      (node (ref "U16") (pin "3") (pinfunction "A2_3") (pintype "unspecified"))
    )
    (net (code "65") (name "Net-(U12-4Y)") (class "Default")
      (node (ref "U12") (pin "11") (pinfunction "4Y_11") (pintype "unspecified"))
      (node (ref "U16") (pin "13") (pinfunction "E3_13") (pintype "unspecified"))
    )
    (net (code "66") (name "Net-(U13-A1)") (class "Default")
      (node (ref "U13") (pin "5") (pinfunction "A1_5") (pintype "unspecified"))
      (node (ref "U5") (pin "3") (pinfunction "1Y_3") (pintype "unspecified"))
    )
    (net (code "67") (name "Net-(U13-A3)") (class "Default")
      (node (ref "U13") (pin "14") (pinfunction "A3_14") (pintype "unspecified"))
      (node (ref "U14") (pin "14") (pinfunction "A3_14") (pintype "unspecified"))
      (node (ref "U15") (pin "14") (pinfunction "A3_14") (pintype "unspecified"))
      (node (ref "U16") (pin "14") (pinfunction "A3_14") (pintype "unspecified"))
    )
    (net (code "68") (name "Net-(U13-A4)") (class "Default")
      (node (ref "U13") (pin "12") (pinfunction "A4_12") (pintype "unspecified"))
      (node (ref "U7") (pin "6") (pinfunction "2Y_6") (pintype "unspecified"))
    )
    (net (code "69") (name "Net-(U13-B1)") (class "Default")
      (node (ref "U13") (pin "6") (pinfunction "B1_6") (pintype "unspecified"))
      (node (ref "U2") (pin "4") (pinfunction "E1_4") (pintype "unspecified"))
    )
    (net (code "70") (name "Net-(U13-B2)") (class "Default")
      (node (ref "U13") (pin "2") (pinfunction "B2_2") (pintype "unspecified"))
      (node (ref "U14") (pin "2") (pinfunction "B2_2") (pintype "unspecified"))
      (node (ref "U15") (pin "2") (pinfunction "B2_2") (pintype "unspecified"))
      (node (ref "U16") (pin "2") (pinfunction "B2_2") (pintype "unspecified"))
    )
    (net (code "71") (name "Net-(U13-E1)") (class "Default")
      (node (ref "U13") (pin "4") (pinfunction "E1_4") (pintype "unspecified"))
      (node (ref "U7") (pin "3") (pinfunction "1Y_3") (pintype "unspecified"))
    )
    (net (code "72") (name "Net-(U13-E4)") (class "Default")
      (node (ref "U13") (pin "10") (pinfunction "E4_10") (pintype "unspecified"))
      (node (ref "U2") (pin "1") (pinfunction "E2_1") (pintype "unspecified"))
    )
    (net (code "73") (name "Net-(U14-A1)") (class "Default")
      (node (ref "U14") (pin "5") (pinfunction "A1_5") (pintype "unspecified"))
      (node (ref "U5") (pin "8") (pinfunction "3Y_8") (pintype "unspecified"))
    )
    (net (code "74") (name "Net-(U14-A4)") (class "Default")
      (node (ref "U14") (pin "12") (pinfunction "A4_12") (pintype "unspecified"))
      (node (ref "U7") (pin "11") (pinfunction "4Y_11") (pintype "unspecified"))
    )
    (net (code "75") (name "Net-(U14-B1)") (class "Default")
      (node (ref "U14") (pin "6") (pinfunction "B1_6") (pintype "unspecified"))
      (node (ref "U2") (pin "13") (pinfunction "E3_13") (pintype "unspecified"))
    )
    (net (code "76") (name "Net-(U14-B4)") (class "Default")
      (node (ref "U14") (pin "11") (pinfunction "B4_11") (pintype "unspecified"))
      (node (ref "U5") (pin "11") (pinfunction "4Y_11") (pintype "unspecified"))
    )
    (net (code "77") (name "Net-(U14-E1)") (class "Default")
      (node (ref "U14") (pin "4") (pinfunction "E1_4") (pintype "unspecified"))
      (node (ref "U7") (pin "8") (pinfunction "3Y_8") (pintype "unspecified"))
    )
    (net (code "78") (name "Net-(U14-E4)") (class "Default")
      (node (ref "U14") (pin "10") (pinfunction "E4_10") (pintype "unspecified"))
      (node (ref "U2") (pin "10") (pinfunction "E4_10") (pintype "unspecified"))
    )
    (net (code "79") (name "Net-(U15-A1)") (class "Default")
      (node (ref "U15") (pin "5") (pinfunction "A1_5") (pintype "unspecified"))
      (node (ref "U6") (pin "3") (pinfunction "1Y_3") (pintype "unspecified"))
    )
    (net (code "80") (name "Net-(U15-A4)") (class "Default")
      (node (ref "U15") (pin "12") (pinfunction "A4_12") (pintype "unspecified"))
      (node (ref "U8") (pin "6") (pinfunction "2Y_6") (pintype "unspecified"))
    )
    (net (code "81") (name "Net-(U15-E1)") (class "Default")
      (node (ref "U15") (pin "4") (pinfunction "E1_4") (pintype "unspecified"))
      (node (ref "U8") (pin "3") (pinfunction "1Y_3") (pintype "unspecified"))
    )
    (net (code "82") (name "Net-(U16-A1)") (class "Default")
      (node (ref "U16") (pin "5") (pinfunction "A1_5") (pintype "unspecified"))
      (node (ref "U6") (pin "8") (pinfunction "3Y_8") (pintype "unspecified"))
    )
    (net (code "83") (name "Net-(U16-A4)") (class "Default")
      (node (ref "U16") (pin "12") (pinfunction "A4_12") (pintype "unspecified"))
      (node (ref "U8") (pin "11") (pinfunction "4Y_11") (pintype "unspecified"))
    )
    (net (code "84") (name "Net-(U16-B4)") (class "Default")
      (node (ref "U16") (pin "11") (pinfunction "B4_11") (pintype "unspecified"))
      (node (ref "U6") (pin "11") (pinfunction "4Y_11") (pintype "unspecified"))
    )
    (net (code "85") (name "Net-(U16-E1)") (class "Default")
      (node (ref "U16") (pin "4") (pinfunction "E1_4") (pintype "unspecified"))
      (node (ref "U8") (pin "8") (pinfunction "3Y_8") (pintype "unspecified"))
    )
    (net (code "86") (name "Net-(U17-#OE)") (class "Default")
      (node (ref "U17") (pin "19") (pinfunction "#OE_19") (pintype "unspecified"))
      (node (ref "U26") (pin "1") (pinfunction "1_1") (pintype "unspecified"))
    )
    (net (code "87") (name "Net-(U17-B1)") (class "Default")
      (node (ref "U17") (pin "18") (pinfunction "B1_18") (pintype "unspecified"))
      (node (ref "U23") (pin "4") (pinfunction "4_4") (pintype "unspecified"))
    )
    (net (code "88") (name "Net-(U17-B2)") (class "Default")
      (node (ref "U17") (pin "17") (pinfunction "B2_17") (pintype "unspecified"))
      (node (ref "U23") (pin "3") (pinfunction "3_3") (pintype "unspecified"))
    )
    (net (code "89") (name "Net-(U17-B3)") (class "Default")
      (node (ref "U17") (pin "16") (pinfunction "B3_16") (pintype "unspecified"))
      (node (ref "U23") (pin "2") (pinfunction "2_2") (pintype "unspecified"))
    )
    (net (code "90") (name "Net-(U17-B4)") (class "Default")
      (node (ref "U17") (pin "15") (pinfunction "B4_15") (pintype "unspecified"))
      (node (ref "U23") (pin "1") (pinfunction "1_1") (pintype "unspecified"))
    )
    (net (code "91") (name "Net-(U17-B5)") (class "Default")
      (node (ref "U17") (pin "14") (pinfunction "B5_14") (pintype "unspecified"))
      (node (ref "U22") (pin "4") (pinfunction "4_4") (pintype "unspecified"))
    )
    (net (code "92") (name "Net-(U17-B6)") (class "Default")
      (node (ref "U17") (pin "13") (pinfunction "B6_13") (pintype "unspecified"))
      (node (ref "U22") (pin "3") (pinfunction "3_3") (pintype "unspecified"))
    )
    (net (code "93") (name "Net-(U17-B7)") (class "Default")
      (node (ref "U17") (pin "12") (pinfunction "B7_12") (pintype "unspecified"))
      (node (ref "U22") (pin "2") (pinfunction "2_2") (pintype "unspecified"))
    )
    (net (code "94") (name "Net-(U17-B8)") (class "Default")
      (node (ref "U17") (pin "11") (pinfunction "B8_11") (pintype "unspecified"))
      (node (ref "U22") (pin "1") (pinfunction "1_1") (pintype "unspecified"))
    )
    (net (code "95") (name "unconnected-(U1-C4-Pad9)") (class "Default")
      (node (ref "U1") (pin "9") (pinfunction "C4_9") (pintype "unspecified"))
    )
    (net (code "96") (name "unconnected-(U26-Pad3)") (class "Default")
      (node (ref "U26") (pin "3") (pinfunction "3_3") (pintype "unspecified"))
    )
    (net (code "97") (name "unconnected-(U26-Pad4)") (class "Default")
      (node (ref "U26") (pin "4") (pinfunction "4_4") (pintype "unspecified"))
    )
    (net (code "98") (name "unconnected-(U28-Pad2)") (class "Default")
      (node (ref "U28") (pin "2") (pinfunction "2_2") (pintype "unspecified"))
    )
    (net (code "99") (name "unconnected-(U28-Pad3)") (class "Default")
      (node (ref "U28") (pin "3") (pinfunction "3_3") (pintype "unspecified"))
    )
    (net (code "100") (name "unconnected-(U28-Pad4)") (class "Default")
      (node (ref "U28") (pin "4") (pinfunction "4_4") (pintype "unspecified"))
    )
  )
)
